# 03_AIR724.net
KiCad netlist of a schematic drawn in Altium Designer
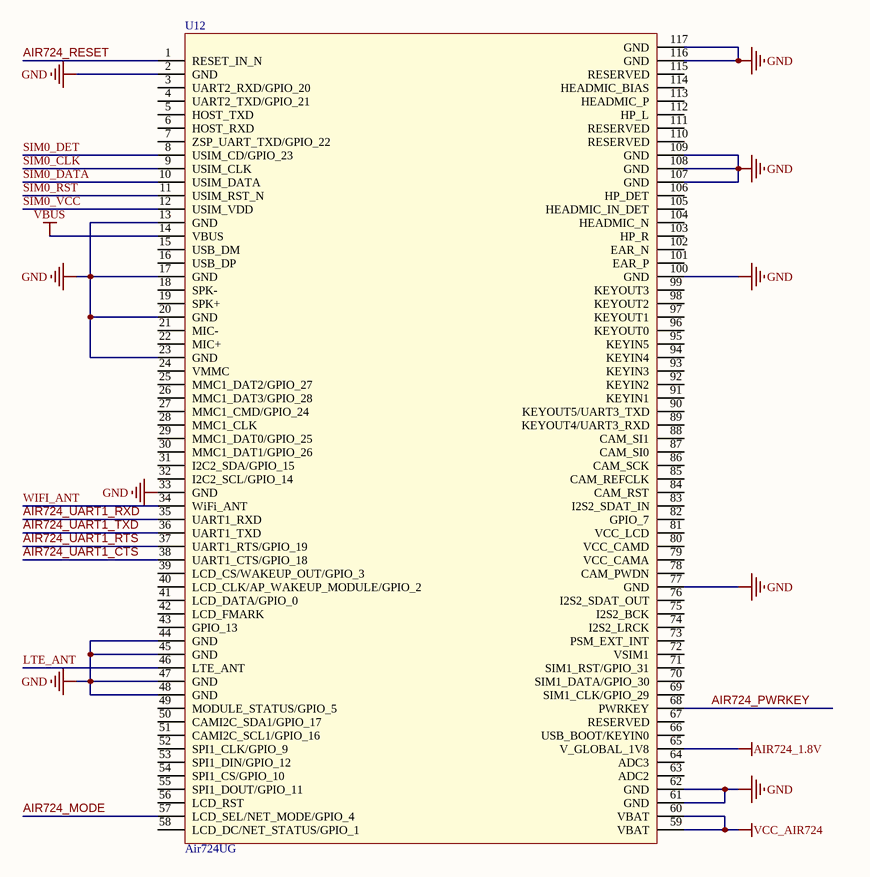
[diagram p0: 03_AIR724.SchDoc]

(export (version "E")
  (design (tool "Eeschema 10.0.6"))
  (components
    (comp (ref "U12")
      (value "Air724UG")
      (footprint "AIR724UG")
      (fields (field (name "MANUFACTURER") "Luat(合宙)") (field (name "MANUFACTURER PART") "Air724UG-NA"))
      (libsource (lib "封装库") (part "Air724UG"))
    )
  )
  (nets
    (net (code "1") (name "/AIR724_MODE") (class "Default")
      (node (ref "U12") (pin "57") (pinfunction "LCD_SEL/NET_MODE/GPIO_4_57") (pintype "passive"))
    )
    (net (code "2") (name "/AIR724_PWRKEY") (class "Default")
      (node (ref "U12") (pin "68") (pinfunction "PWRKEY_68") (pintype "passive"))
    )
    (net (code "3") (name "/AIR724_RESET") (class "Default")
      (node (ref "U12") (pin "1") (pinfunction "RESET_IN_N_1") (pintype "passive"))
    )
    (net (code "4") (name "/AIR724_UART1_CTS") (class "Default")
      (node (ref "U12") (pin "38") (pinfunction "UART1_CTS/GPIO_18_38") (pintype "passive"))
    )
    (net (code "5") (name "/AIR724_UART1_RTS") (class "Default")
      (node (ref "U12") (pin "37") (pinfunction "UART1_RTS/GPIO_19_37") (pintype "passive"))
    )
    (net (code "6") (name "/AIR724_UART1_RXD") (class "Default")
      (node (ref "U12") (pin "35") (pinfunction "UART1_RXD_35") (pintype "passive"))
    )
    (net (code "7") (name "/AIR724_UART1_TXD") (class "Default")
      (node (ref "U12") (pin "36") (pinfunction "UART1_TXD_36") (pintype "passive"))
    )
    (net (code "8") (name "/LTE_ANT") (class "Default")
      (node (ref "U12") (pin "46") (pinfunction "LTE_ANT_46") (pintype "passive"))
    )
    (net (code "9") (name "/SIM0_CLK") (class "Default")
      (node (ref "U12") (pin "9") (pinfunction "USIM_CLK_9") (pintype "passive"))
    )
    (net (code "10") (name "/SIM0_DATA") (class "Default")
      (node (ref "U12") (pin "10") (pinfunction "USIM_DATA_10") (pintype "passive"))
    )
    (net (code "11") (name "/SIM0_DET") (class "Default")
      (node (ref "U12") (pin "8") (pinfunction "USIM_CD/GPIO_23_8") (pintype "passive"))
    )
    (net (code "12") (name "/SIM0_RST") (class "Default")
      (node (ref "U12") (pin "11") (pinfunction "USIM_RST_N_11") (pintype "passive"))
    )
    (net (code "13") (name "/SIM0_VCC") (class "Default")
      (node (ref "U12") (pin "12") (pinfunction "USIM_VDD_12") (pintype "passive"))
    )
    (net (code "14") (name "/WIFI_ANT") (class "Default")
      (node (ref "U12") (pin "34") (pinfunction "WiFi_ANT_34") (pintype "passive"))
    )
    (net (code "15") (name "AIR724_1.8V") (class "Default")
      (node (ref "U12") (pin "65") (pinfunction "V_GLOBAL_1V8_65") (pintype "passive"))
    )
    (net (code "16") (name "GND") (class "Default")
      (node (ref "U12") (pin "100") (pinfunction "GND_100") (pintype "passive"))
      (node (ref "U12") (pin "107") (pinfunction "GND_107") (pintype "passive"))
      (node (ref "U12") (pin "108") (pinfunction "GND_108") (pintype "passive"))
      (node (ref "U12") (pin "109") (pinfunction "GND_109") (pintype "passive"))
      (node (ref "U12") (pin "116") (pinfunction "GND_116") (pintype "passive"))
      (node (ref "U12") (pin "117") (pinfunction "GND_117") (pintype "passive"))
      (node (ref "U12") (pin "13") (pinfunction "GND_13") (pintype "passive"))
      (node (ref "U12") (pin "17") (pinfunction "GND_17") (pintype "passive"))
      (node (ref "U12") (pin "2") (pinfunction "GND_2") (pintype "passive"))
      (node (ref "U12") (pin "20") (pinfunction "GND_20") (pintype "passive"))
      (node (ref "U12") (pin "23") (pinfunction "GND_23") (pintype "passive"))
      (node (ref "U12") (pin "33") (pinfunction "GND_33") (pintype "passive"))
      (node (ref "U12") (pin "44") (pinfunction "GND_44") (pintype "passive"))
      (node (ref "U12") (pin "45") (pinfunction "GND_45") (pintype "passive"))
      (node (ref "U12") (pin "47") (pinfunction "GND_47") (pintype "passive"))
      (node (ref "U12") (pin "48") (pinfunction "GND_48") (pintype "passive"))
      (node (ref "U12") (pin "61") (pinfunction "GND_61") (pintype "passive"))
      (node (ref "U12") (pin "62") (pinfunction "GND_62") (pintype "passive"))
      (node (ref "U12") (pin "77") (pinfunction "GND_77") (pintype "passive"))
    )
    (net (code "17") (name "VBUS") (class "Default")
      (node (ref "U12") (pin "14") (pinfunction "VBUS_14") (pintype "passive"))
    )
    (net (code "18") (name "VCC_AIR724") (class "Default")
      (node (ref "U12") (pin "59") (pinfunction "VBAT_59") (pintype "passive"))
      (node (ref "U12") (pin "60") (pinfunction "VBAT_60") (pintype "passive"))
    )
    (net (code "19") (name "unconnected-(U12-ADC2-Pad63)") (class "Default")
      (node (ref "U12") (pin "63") (pinfunction "ADC2_63") (pintype "passive"))
    )
    (net (code "20") (name "unconnected-(U12-ADC3-Pad64)") (class "Default")
      (node (ref "U12") (pin "64") (pinfunction "ADC3_64") (pintype "passive"))
    )
    (net (code "21") (name "unconnected-(U12-CAMI2C_SCL1{slash}GPIO_16-Pad51)") (class "Default")
      (node (ref "U12") (pin "51") (pinfunction "CAMI2C_SCL1/GPIO_16_51") (pintype "passive"))
    )
    (net (code "22") (name "unconnected-(U12-CAMI2C_SDA1{slash}GPIO_17-Pad50)") (class "Default")
      (node (ref "U12") (pin "50") (pinfunction "CAMI2C_SDA1/GPIO_17_50") (pintype "passive"))
    )
    (net (code "23") (name "unconnected-(U12-CAM_PWDN-Pad78)") (class "Default")
      (node (ref "U12") (pin "78") (pinfunction "CAM_PWDN_78") (pintype "passive"))
    )
    (net (code "24") (name "unconnected-(U12-CAM_REFCLK-Pad85)") (class "Default")
      (node (ref "U12") (pin "85") (pinfunction "CAM_REFCLK_85") (pintype "passive"))
    )
    (net (code "25") (name "unconnected-(U12-CAM_RST-Pad84)") (class "Default")
      (node (ref "U12") (pin "84") (pinfunction "CAM_RST_84") (pintype "passive"))
    )
    (net (code "26") (name "unconnected-(U12-CAM_SCK-Pad86)") (class "Default")
      (node (ref "U12") (pin "86") (pinfunction "CAM_SCK_86") (pintype "passive"))
    )
    (net (code "27") (name "unconnected-(U12-CAM_SI0-Pad87)") (class "Default")
      (node (ref "U12") (pin "87") (pinfunction "CAM_SI0_87") (pintype "passive"))
    )
    (net (code "28") (name "unconnected-(U12-CAM_SI1-Pad88)") (class "Default")
      (node (ref "U12") (pin "88") (pinfunction "CAM_SI1_88") (pintype "passive"))
    )
    (net (code "29") (name "unconnected-(U12-EAR_N-Pad102)") (class "Default")
      (node (ref "U12") (pin "102") (pinfunction "EAR_N_102") (pintype "passive"))
    )
    (net (code "30") (name "unconnected-(U12-EAR_P-Pad101)") (class "Default")
      (node (ref "U12") (pin "101") (pinfunction "EAR_P_101") (pintype "passive"))
    )
    (net (code "31") (name "unconnected-(U12-GPIO_7-Pad82)") (class "Default")
      (node (ref "U12") (pin "82") (pinfunction "GPIO_7_82") (pintype "passive"))
    )
    (net (code "32") (name "unconnected-(U12-GPIO_13-Pad43)") (class "Default")
      (node (ref "U12") (pin "43") (pinfunction "GPIO_13_43") (pintype "passive"))
    )
    (net (code "33") (name "unconnected-(U12-HEADMIC_BIAS-Pad114)") (class "Default")
      (node (ref "U12") (pin "114") (pinfunction "HEADMIC_BIAS_114") (pintype "passive"))
    )
    (net (code "34") (name "unconnected-(U12-HEADMIC_IN_DET-Pad105)") (class "Default")
      (node (ref "U12") (pin "105") (pinfunction "HEADMIC_IN_DET_105") (pintype "passive"))
    )
    (net (code "35") (name "unconnected-(U12-HEADMIC_N-Pad104)") (class "Default")
      (node (ref "U12") (pin "104") (pinfunction "HEADMIC_N_104") (pintype "passive"))
    )
    (net (code "36") (name "unconnected-(U12-HEADMIC_P-Pad113)") (class "Default")
      (node (ref "U12") (pin "113") (pinfunction "HEADMIC_P_113") (pintype "passive"))
    )
    (net (code "37") (name "unconnected-(U12-HOST_RXD-Pad6)") (class "Default")
      (node (ref "U12") (pin "6") (pinfunction "HOST_RXD_6") (pintype "passive"))
    )
    (net (code "38") (name "unconnected-(U12-HOST_TXD-Pad5)") (class "Default")
      (node (ref "U12") (pin "5") (pinfunction "HOST_TXD_5") (pintype "passive"))
    )
    (net (code "39") (name "unconnected-(U12-HP_DET-Pad106)") (class "Default")
      (node (ref "U12") (pin "106") (pinfunction "HP_DET_106") (pintype "passive"))
    )
    (net (code "40") (name "unconnected-(U12-HP_L-Pad112)") (class "Default")
      (node (ref "U12") (pin "112") (pinfunction "HP_L_112") (pintype "passive"))
    )
    (net (code "41") (name "unconnected-(U12-HP_R-Pad103)") (class "Default")
      (node (ref "U12") (pin "103") (pinfunction "HP_R_103") (pintype "passive"))
    )
    (net (code "42") (name "unconnected-(U12-I2C2_SCL{slash}GPIO_14-Pad32)") (class "Default")
      (node (ref "U12") (pin "32") (pinfunction "I2C2_SCL/GPIO_14_32") (pintype "passive"))
    )
    (net (code "43") (name "unconnected-(U12-I2C2_SDA{slash}GPIO_15-Pad31)") (class "Default")
      (node (ref "U12") (pin "31") (pinfunction "I2C2_SDA/GPIO_15_31") (pintype "passive"))
    )
    (net (code "44") (name "unconnected-(U12-I2S2_BCK-Pad75)") (class "Default")
      (node (ref "U12") (pin "75") (pinfunction "I2S2_BCK_75") (pintype "passive"))
    )
    (net (code "45") (name "unconnected-(U12-I2S2_LRCK-Pad74)") (class "Default")
      (node (ref "U12") (pin "74") (pinfunction "I2S2_LRCK_74") (pintype "passive"))
    )
    (net (code "46") (name "unconnected-(U12-I2S2_SDAT_IN-Pad83)") (class "Default")
      (node (ref "U12") (pin "83") (pinfunction "I2S2_SDAT_IN_83") (pintype "passive"))
    )
    (net (code "47") (name "unconnected-(U12-I2S2_SDAT_OUT-Pad76)") (class "Default")
      (node (ref "U12") (pin "76") (pinfunction "I2S2_SDAT_OUT_76") (pintype "passive"))
    )
    (net (code "48") (name "unconnected-(U12-KEYIN1-Pad91)") (class "Default")
      (node (ref "U12") (pin "91") (pinfunction "KEYIN1_91") (pintype "passive"))
    )
    (net (code "49") (name "unconnected-(U12-KEYIN2-Pad92)") (class "Default")
      (node (ref "U12") (pin "92") (pinfunction "KEYIN2_92") (pintype "passive"))
    )
    (net (code "50") (name "unconnected-(U12-KEYIN3-Pad93)") (class "Default")
      (node (ref "U12") (pin "93") (pinfunction "KEYIN3_93") (pintype "passive"))
    )
    (net (code "51") (name "unconnected-(U12-KEYIN4-Pad94)") (class "Default")
      (node (ref "U12") (pin "94") (pinfunction "KEYIN4_94") (pintype "passive"))
    )
    (net (code "52") (name "unconnected-(U12-KEYIN5-Pad95)") (class "Default")
      (node (ref "U12") (pin "95") (pinfunction "KEYIN5_95") (pintype "passive"))
    )
    (net (code "53") (name "unconnected-(U12-KEYOUT0-Pad96)") (class "Default")
      (node (ref "U12") (pin "96") (pinfunction "KEYOUT0_96") (pintype "passive"))
    )
    (net (code "54") (name "unconnected-(U12-KEYOUT1-Pad97)") (class "Default")
      (node (ref "U12") (pin "97") (pinfunction "KEYOUT1_97") (pintype "passive"))
    )
    (net (code "55") (name "unconnected-(U12-KEYOUT2-Pad98)") (class "Default")
      (node (ref "U12") (pin "98") (pinfunction "KEYOUT2_98") (pintype "passive"))
    )
    (net (code "56") (name "unconnected-(U12-KEYOUT3-Pad99)") (class "Default")
      (node (ref "U12") (pin "99") (pinfunction "KEYOUT3_99") (pintype "passive"))
    )
    (net (code "57") (name "unconnected-(U12-KEYOUT4{slash}UART3_RXD-Pad89)") (class "Default")
      (node (ref "U12") (pin "89") (pinfunction "KEYOUT4/UART3_RXD_89") (pintype "passive"))
    )
    (net (code "58") (name "unconnected-(U12-KEYOUT5{slash}UART3_TXD-Pad90)") (class "Default")
      (node (ref "U12") (pin "90") (pinfunction "KEYOUT5/UART3_TXD_90") (pintype "passive"))
    )
    (net (code "59") (name "unconnected-(U12-LCD_CLK{slash}AP_WAKEUP_MODULE{slash}GPIO_2-Pad40)") (class "Default")
      (node (ref "U12") (pin "40") (pinfunction "LCD_CLK/AP_WAKEUP_MODULE/GPIO_2_40") (pintype "passive"))
    )
    (net (code "60") (name "unconnected-(U12-LCD_CS{slash}WAKEUP_OUT{slash}GPIO_3-Pad39)") (class "Default")
      (node (ref "U12") (pin "39") (pinfunction "LCD_CS/WAKEUP_OUT/GPIO_3_39") (pintype "passive"))
    )
    (net (code "61") (name "unconnected-(U12-LCD_DATA{slash}GPIO_0-Pad41)") (class "Default")
      (node (ref "U12") (pin "41") (pinfunction "LCD_DATA/GPIO_0_41") (pintype "passive"))
    )
    (net (code "62") (name "unconnected-(U12-LCD_DC{slash}NET_STATUS{slash}GPIO_1-Pad58)") (class "Default")
      (node (ref "U12") (pin "58") (pinfunction "LCD_DC/NET_STATUS/GPIO_1_58") (pintype "passive"))
    )
    (net (code "63") (name "unconnected-(U12-LCD_FMARK-Pad42)") (class "Default")
      (node (ref "U12") (pin "42") (pinfunction "LCD_FMARK_42") (pintype "passive"))
    )
    (net (code "64") (name "unconnected-(U12-LCD_RST-Pad56)") (class "Default")
      (node (ref "U12") (pin "56") (pinfunction "LCD_RST_56") (pintype "passive"))
    )
    (net (code "65") (name "unconnected-(U12-MIC+-Pad22)") (class "Default")
      (node (ref "U12") (pin "22") (pinfunction "MIC+_22") (pintype "passive"))
    )
    (net (code "66") (name "unconnected-(U12-MIC--Pad21)") (class "Default")
      (node (ref "U12") (pin "21") (pinfunction "MIC-_21") (pintype "passive"))
    )
    (net (code "67") (name "unconnected-(U12-MMC1_CLK-Pad28)") (class "Default")
      (node (ref "U12") (pin "28") (pinfunction "MMC1_CLK_28") (pintype "passive"))
    )
    (net (code "68") (name "unconnected-(U12-MMC1_CMD{slash}GPIO_24-Pad27)") (class "Default")
      (node (ref "U12") (pin "27") (pinfunction "MMC1_CMD/GPIO_24_27") (pintype "passive"))
    )
    (net (code "69") (name "unconnected-(U12-MMC1_DAT0{slash}GPIO_25-Pad29)") (class "Default")
      (node (ref "U12") (pin "29") (pinfunction "MMC1_DAT0/GPIO_25_29") (pintype "passive"))
    )
    (net (code "70") (name "unconnected-(U12-MMC1_DAT1{slash}GPIO_26-Pad30)") (class "Default")
      (node (ref "U12") (pin "30") (pinfunction "MMC1_DAT1/GPIO_26_30") (pintype "passive"))
    )
    (net (code "71") (name "unconnected-(U12-MMC1_DAT2{slash}GPIO_27-Pad25)") (class "Default")
      (node (ref "U12") (pin "25") (pinfunction "MMC1_DAT2/GPIO_27_25") (pintype "passive"))
    )
    (net (code "72") (name "unconnected-(U12-MMC1_DAT3{slash}GPIO_28-Pad26)") (class "Default")
      (node (ref "U12") (pin "26") (pinfunction "MMC1_DAT3/GPIO_28_26") (pintype "passive"))
    )
    (net (code "73") (name "unconnected-(U12-MODULE_STATUS{slash}GPIO_5-Pad49)") (class "Default")
      (node (ref "U12") (pin "49") (pinfunction "MODULE_STATUS/GPIO_5_49") (pintype "passive"))
    )
    (net (code "74") (name "unconnected-(U12-PSM_EXT_INT-Pad73)") (class "Default")
      (node (ref "U12") (pin "73") (pinfunction "PSM_EXT_INT_73") (pintype "passive"))
    )
    (net (code "75") (name "unconnected-(U12-RESERVED-Pad67)") (class "Default")
      (node (ref "U12") (pin "67") (pinfunction "RESERVED_67") (pintype "passive"))
    )
    (net (code "76") (name "unconnected-(U12-RESERVED-Pad110)") (class "Default")
      (node (ref "U12") (pin "110") (pinfunction "RESERVED_110") (pintype "passive"))
    )
    (net (code "77") (name "unconnected-(U12-RESERVED-Pad111)") (class "Default")
      (node (ref "U12") (pin "111") (pinfunction "RESERVED_111") (pintype "passive"))
    )
    (net (code "78") (name "unconnected-(U12-RESERVED-Pad115)") (class "Default")
      (node (ref "U12") (pin "115") (pinfunction "RESERVED_115") (pintype "passive"))
    )
    (net (code "79") (name "unconnected-(U12-SIM1_CLK{slash}GPIO_29-Pad69)") (class "Default")
      (node (ref "U12") (pin "69") (pinfunction "SIM1_CLK/GPIO_29_69") (pintype "passive"))
    )
    (net (code "80") (name "unconnected-(U12-SIM1_DATA{slash}GPIO_30-Pad70)") (class "Default")
      (node (ref "U12") (pin "70") (pinfunction "SIM1_DATA/GPIO_30_70") (pintype "passive"))
    )
    (net (code "81") (name "unconnected-(U12-SIM1_RST{slash}GPIO_31-Pad71)") (class "Default")
      (node (ref "U12") (pin "71") (pinfunction "SIM1_RST/GPIO_31_71") (pintype "passive"))
    )
    (net (code "82") (name "unconnected-(U12-SPI1_CLK{slash}GPIO_9-Pad52)") (class "Default")
      (node (ref "U12") (pin "52") (pinfunction "SPI1_CLK/GPIO_9_52") (pintype "passive"))
    )
    (net (code "83") (name "unconnected-(U12-SPI1_CS{slash}GPIO_10-Pad54)") (class "Default")
      (node (ref "U12") (pin "54") (pinfunction "SPI1_CS/GPIO_10_54") (pintype "passive"))
    )
    (net (code "84") (name "unconnected-(U12-SPI1_DIN{slash}GPIO_12-Pad53)") (class "Default")
      (node (ref "U12") (pin "53") (pinfunction "SPI1_DIN/GPIO_12_53") (pintype "passive"))
    )
    (net (code "85") (name "unconnected-(U12-SPI1_DOUT{slash}GPIO_11-Pad55)") (class "Default")
      (node (ref "U12") (pin "55") (pinfunction "SPI1_DOUT/GPIO_11_55") (pintype "passive"))
    )
    (net (code "86") (name "unconnected-(U12-SPK+-Pad19)") (class "Default")
      (node (ref "U12") (pin "19") (pinfunction "SPK+_19") (pintype "passive"))
    )
    (net (code "87") (name "unconnected-(U12-SPK--Pad18)") (class "Default")
      (node (ref "U12") (pin "18") (pinfunction "SPK-_18") (pintype "passive"))
    )
    (net (code "88") (name "unconnected-(U12-UART2_RXD{slash}GPIO_20-Pad3)") (class "Default")
      (node (ref "U12") (pin "3") (pinfunction "UART2_RXD/GPIO_20_3") (pintype "passive"))
    )
    (net (code "89") (name "unconnected-(U12-UART2_TXD{slash}GPIO_21-Pad4)") (class "Default")
      (node (ref "U12") (pin "4") (pinfunction "UART2_TXD/GPIO_21_4") (pintype "passive"))
    )
    (net (code "90") (name "unconnected-(U12-USB_BOOT{slash}KEYIN0-Pad66)") (class "Default")
      (node (ref "U12") (pin "66") (pinfunction "USB_BOOT/KEYIN0_66") (pintype "passive"))
    )
    (net (code "91") (name "unconnected-(U12-USB_DM-Pad15)") (class "Default")
      (node (ref "U12") (pin "15") (pinfunction "USB_DM_15") (pintype "passive"))
    )
    (net (code "92") (name "unconnected-(U12-USB_DP-Pad16)") (class "Default")
      (node (ref "U12") (pin "16") (pinfunction "USB_DP_16") (pintype "passive"))
    )
    (net (code "93") (name "unconnected-(U12-VCC_CAMA-Pad79)") (class "Default")
      (node (ref "U12") (pin "79") (pinfunction "VCC_CAMA_79") (pintype "passive"))
    )
    (net (code "94") (name "unconnected-(U12-VCC_CAMD-Pad80)") (class "Default")
      (node (ref "U12") (pin "80") (pinfunction "VCC_CAMD_80") (pintype "passive"))
    )
    (net (code "95") (name "unconnected-(U12-VCC_LCD-Pad81)") (class "Default")
      (node (ref "U12") (pin "81") (pinfunction "VCC_LCD_81") (pintype "passive"))
    )
    (net (code "96") (name "unconnected-(U12-VMMC-Pad24)") (class "Default")
      (node (ref "U12") (pin "24") (pinfunction "VMMC_24") (pintype "passive"))
    )
    (net (code "97") (name "unconnected-(U12-VSIM1-Pad72)") (class "Default")
      (node (ref "U12") (pin "72") (pinfunction "VSIM1_72") (pintype "passive"))
    )
    (net (code "98") (name "unconnected-(U12-ZSP_UART_TXD{slash}GPIO_22-Pad7)") (class "Default")
      (node (ref "U12") (pin "7") (pinfunction "ZSP_UART_TXD/GPIO_22_7") (pintype "passive"))
    )
  )
)
